# BQ34110.net
KiCad netlist of a schematic drawn in Altium Designer
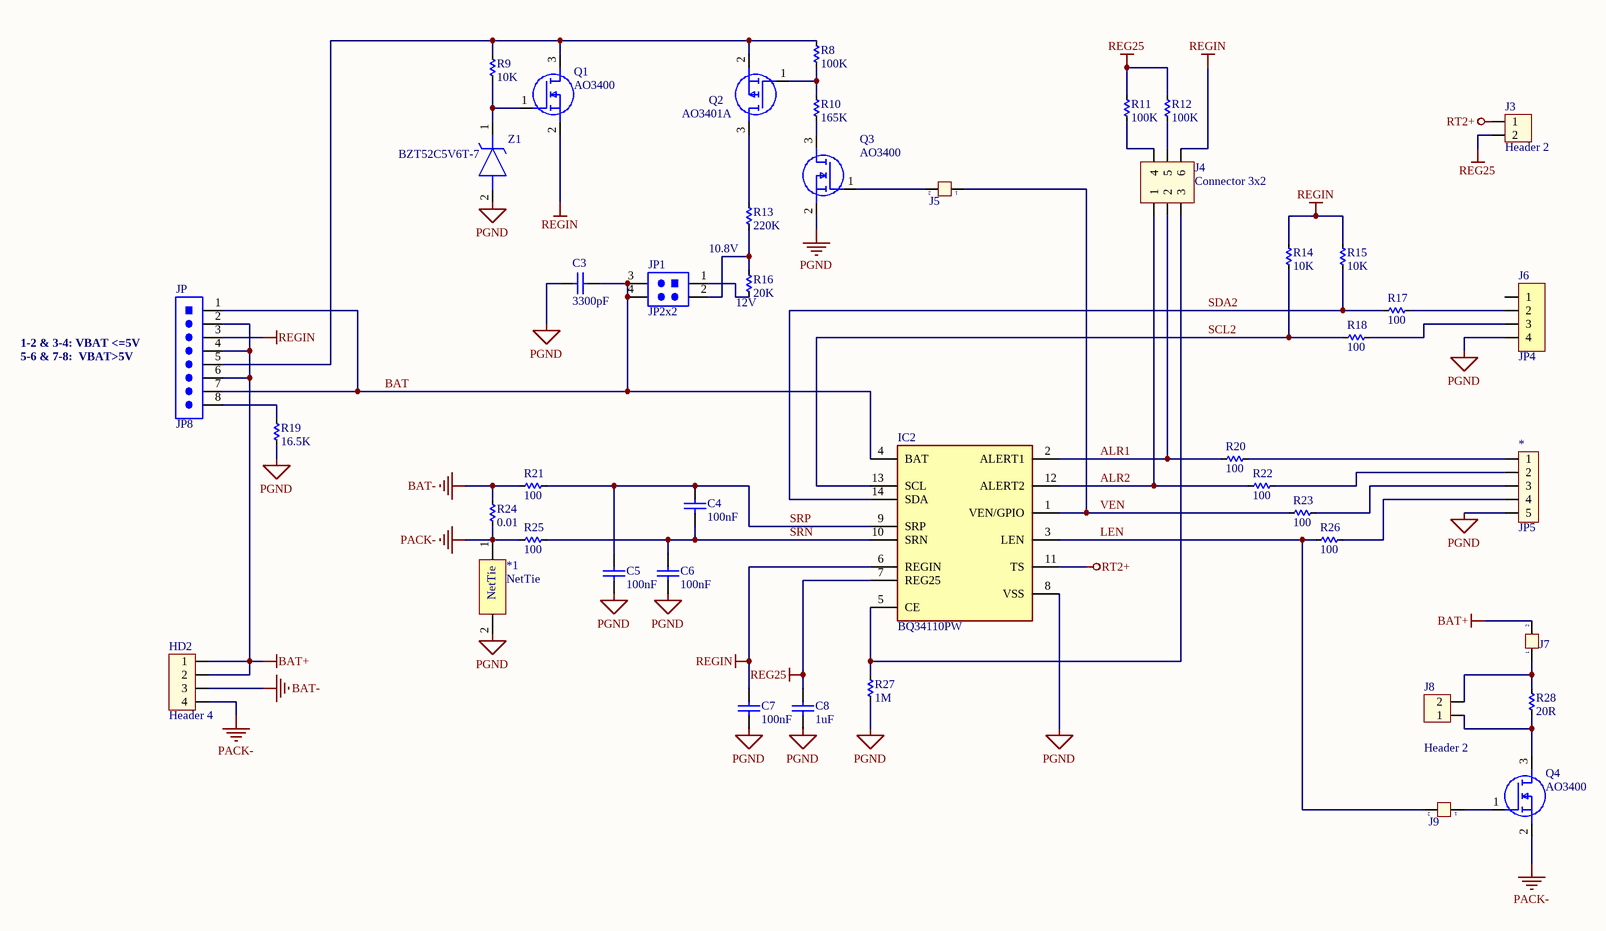
[diagram p0: BQ34110.SchDoc]

(export (version "E")
  (design (tool "Eeschema 10.0.6"))
  (components
    (comp (ref "*") (value "JP5") (footprint "JP5") (libsource (lib "syhaunguyen") (part "JP5")))
    (comp (ref "*1") (value "NetTie") (footprint "NetTie") (libsource (lib "PhanBach") (part "NetTie")))
    (comp (ref "C3")
      (value "3300pF")
      (footprint "0805 CAP")
      (fields (field (name "PUBLISHER") "Altium Limited"))
      (libsource (lib "ThinhNguyenLib") (part "CAP CERAMIC"))
    )
    (comp (ref "C4")
      (value "100nF")
      (footprint "0805 CAP")
      (fields (field (name "PUBLISHER") "Altium Limited"))
      (libsource (lib "ThinhNguyenLib") (part "CAP CERAMIC"))
    )
    (comp (ref "C5")
      (value "100nF")
      (footprint "0805 CAP")
      (fields (field (name "PUBLISHER") "Altium Limited"))
      (libsource (lib "ThinhNguyenLib") (part "CAP CERAMIC"))
    )
    (comp (ref "C6")
      (value "100nF")
      (footprint "0805 CAP")
      (fields (field (name "PUBLISHER") "Altium Limited"))
      (libsource (lib "ThinhNguyenLib") (part "CAP CERAMIC"))
    )
    (comp (ref "C7")
      (value "100nF")
      (footprint "0805 CAP")
      (fields (field (name "PUBLISHER") "Altium Limited"))
      (libsource (lib "ThinhNguyenLib") (part "CAP CERAMIC"))
    )
    (comp (ref "C8")
      (value "1uF")
      (footprint "0805 CAP")
      (fields (field (name "PUBLISHER") "Altium Limited"))
      (libsource (lib "ThinhNguyenLib") (part "CAP CERAMIC"))
    )
    (comp (ref "HD2")
      (value "Header 4")
      (footprint "HED4")
      (description "Header 4 (Green)")
      (libsource (lib "syhaunguyen") (part "Hed4"))
    )
    (comp (ref "IC2")
      (value "BQ34110PW")
      (footprint "SamacSys:SOP65P640X120-14N")
      (description "Integrated Circuit")
      (fields (field (name "MOUSER PART NUMBER") "595-BQ34110PW"))
      (libsource (lib "SamacSys") (part "BQ34110PW"))
    )
    (comp (ref "J3")
      (value "Header 2")
      (footprint "HED2B")
      (description "Header 2 (Green)")
      (libsource (lib "syhaunguyen") (part "Hed2"))
    )
    (comp (ref "J4")
      (value "Connector 3x2")
      (footprint "JP3x2")
      (libsource (lib "syhaunguyen") (part "JP3x2"))
    )
    (comp (ref "J5") (value "Jumper 2") (footprint "JP2") (libsource (lib "library") (part "JP 2")))
    (comp (ref "J6")
      (value "JP4")
      (footprint "JP4-C1T")
      (description "WR-PHD 2.54 mm Angled Socket Header")
      (fields
        (field (name "MANUFACTURER") "Würth Elektronik eiSos GmbH")
        (field (name "PARTNO") "613004143121")
        (field (name "CREATED BY") "Karrer Zheng")
      )
      (libsource (lib "LIBRARY1") (part "JP4"))
    )
    (comp (ref "J7") (value "Jumper 2") (footprint "JP2") (libsource (lib "") (part "JP 2_1")))
    (comp (ref "J8")
      (value "Header 2")
      (footprint "HED2B")
      (description "Header 2 (Green)")
      (libsource (lib "") (part "Hed2_1"))
    )
    (comp (ref "J9") (value "Jumper 2") (footprint "JP2") (libsource (lib "library") (part "JP 2")))
    (comp (ref "JP") (value "JP8") (footprint "JP8") (libsource (lib "PhanBach") (part "JP8")))
    (comp (ref "JP1") (value "JP2x2") (footprint "JP2X2") (libsource (lib "PhanBach") (part "JP2x2")))
    (comp (ref "Q1")
      (value "AO3400")
      (footprint "SamacSys:SOT95P280X125-3N")
      (description "MOSFET (N-Channel)")
      (libsource (lib "*") (part "AO3400"))
    )
    (comp (ref "Q2")
      (value "AO3401A")
      (footprint "SamacSys:SOT95P280X125-3N")
      (description "MOSFET (P-Channel)")
      (libsource (lib "*") (part "AO3401A"))
    )
    (comp (ref "Q3")
      (value "AO3400")
      (footprint "SamacSys:SOT95P280X125-3N")
      (description "MOSFET (N-Channel)")
      (libsource (lib "*") (part "AO3400"))
    )
    (comp (ref "Q4")
      (value "AO3400")
      (footprint "SamacSys:SOT95P280X125-3N")
      (description "MOSFET (N-Channel)")
      (libsource (lib "*") (part "AO3400"))
    )
    (comp (ref "R8")
      (value "100K")
      (footprint "RES-SMD-0805")
      (description "Resistor")
      (fields
        (field (name "MANUFACTURER") "Generic Components")
        (field (name "PUBLISHER") "Altium Hobart Technology Centre")
      )
      (libsource (lib "LIBRARY1") (part "Res-SMD"))
    )
    (comp (ref "R9")
      (value "10K")
      (footprint "RES-SMD-0805")
      (description "Resistor")
      (fields
        (field (name "MANUFACTURER") "Generic Components")
        (field (name "PUBLISHER") "Altium Hobart Technology Centre")
      )
      (libsource (lib "LIBRARY1") (part "Res-SMD"))
    )
    (comp (ref "R10")
      (value "165K")
      (footprint "RES-SMD-0805")
      (description "Resistor")
      (fields
        (field (name "MANUFACTURER") "Generic Components")
        (field (name "PUBLISHER") "Altium Hobart Technology Centre")
      )
      (libsource (lib "LIBRARY1") (part "Res-SMD"))
    )
    (comp (ref "R11")
      (value "100K")
      (footprint "RES-SMD-0805")
      (description "Resistor")
      (fields
        (field (name "MANUFACTURER") "Generic Components")
        (field (name "PUBLISHER") "Altium Hobart Technology Centre")
      )
      (libsource (lib "LIBRARY1") (part "Res-SMD"))
    )
    (comp (ref "R12")
      (value "100K")
      (footprint "RES-SMD-0805")
      (description "Resistor")
      (fields
        (field (name "MANUFACTURER") "Generic Components")
        (field (name "PUBLISHER") "Altium Hobart Technology Centre")
      )
      (libsource (lib "LIBRARY1") (part "Res-SMD"))
    )
    (comp (ref "R13")
      (value "220K")
      (footprint "RES-SMD-0805")
      (description "Resistor")
      (fields
        (field (name "MANUFACTURER") "Generic Components")
        (field (name "PUBLISHER") "Altium Hobart Technology Centre")
      )
      (libsource (lib "LIBRARY1") (part "Res-SMD"))
    )
    (comp (ref "R14")
      (value "10K")
      (footprint "RES-SMD-0805")
      (description "Resistor")
      (fields
        (field (name "MANUFACTURER") "Generic Components")
        (field (name "PUBLISHER") "Altium Hobart Technology Centre")
      )
      (libsource (lib "LIBRARY1") (part "Res-SMD"))
    )
    (comp (ref "R15")
      (value "10K")
      (footprint "RES-SMD-0805")
      (description "Resistor")
      (fields
        (field (name "MANUFACTURER") "Generic Components")
        (field (name "PUBLISHER") "Altium Hobart Technology Centre")
      )
      (libsource (lib "LIBRARY1") (part "Res-SMD"))
    )
    (comp (ref "R16")
      (value "20K")
      (footprint "RES-SMD-0805")
      (description "Resistor")
      (fields
        (field (name "MANUFACTURER") "Generic Components")
        (field (name "PUBLISHER") "Altium Hobart Technology Centre")
      )
      (libsource (lib "LIBRARY1") (part "Res-SMD"))
    )
    (comp (ref "R17")
      (value "100")
      (footprint "RES-SMD-0805")
      (description "Resistor")
      (fields
        (field (name "MANUFACTURER") "Generic Components")
        (field (name "PUBLISHER") "Altium Hobart Technology Centre")
      )
      (libsource (lib "LIBRARY1") (part "Res-SMD"))
    )
    (comp (ref "R18")
      (value "100")
      (footprint "RES-SMD-0805")
      (description "Resistor")
      (fields
        (field (name "MANUFACTURER") "Generic Components")
        (field (name "PUBLISHER") "Altium Hobart Technology Centre")
      )
      (libsource (lib "LIBRARY1") (part "Res-SMD"))
    )
    (comp (ref "R19")
      (value "16.5K")
      (footprint "RES-SMD-0805")
      (description "Resistor")
      (fields
        (field (name "MANUFACTURER") "Generic Components")
        (field (name "PUBLISHER") "Altium Hobart Technology Centre")
      )
      (libsource (lib "LIBRARY1") (part "Res-SMD"))
    )
    (comp (ref "R20")
      (value "100")
      (footprint "RES-SMD-0805")
      (description "Resistor")
      (fields
        (field (name "MANUFACTURER") "Generic Components")
        (field (name "PUBLISHER") "Altium Hobart Technology Centre")
      )
      (libsource (lib "LIBRARY1") (part "Res-SMD"))
    )
    (comp (ref "R21")
      (value "100")
      (footprint "RES-SMD-0805")
      (description "Resistor")
      (fields
        (field (name "MANUFACTURER") "Generic Components")
        (field (name "PUBLISHER") "Altium Hobart Technology Centre")
      )
      (libsource (lib "LIBRARY1") (part "Res-SMD"))
    )
    (comp (ref "R22")
      (value "100")
      (footprint "RES-SMD-0805")
      (description "Resistor")
      (fields
        (field (name "MANUFACTURER") "Generic Components")
        (field (name "PUBLISHER") "Altium Hobart Technology Centre")
      )
      (libsource (lib "LIBRARY1") (part "Res-SMD"))
    )
    (comp (ref "R23")
      (value "100")
      (footprint "RES-SMD-0805")
      (description "Resistor")
      (fields
        (field (name "MANUFACTURER") "Generic Components")
        (field (name "PUBLISHER") "Altium Hobart Technology Centre")
      )
      (libsource (lib "LIBRARY1") (part "Res-SMD"))
    )
    (comp (ref "R24")
      (value "0.01")
      (footprint "RES-SMD-0805")
      (description "Resistor")
      (fields
        (field (name "MANUFACTURER") "Generic Components")
        (field (name "PUBLISHER") "Altium Hobart Technology Centre")
      )
      (libsource (lib "LIBRARY1") (part "Res-SMD"))
    )
    (comp (ref "R25")
      (value "100")
      (footprint "RES-SMD-0805")
      (description "Resistor")
      (fields
        (field (name "MANUFACTURER") "Generic Components")
        (field (name "PUBLISHER") "Altium Hobart Technology Centre")
      )
      (libsource (lib "LIBRARY1") (part "Res-SMD"))
    )
    (comp (ref "R26")
      (value "100")
      (footprint "RES-SMD-0805")
      (description "Resistor")
      (fields
        (field (name "MANUFACTURER") "Generic Components")
        (field (name "PUBLISHER") "Altium Hobart Technology Centre")
      )
      (libsource (lib "LIBRARY1") (part "Res-SMD"))
    )
    (comp (ref "R27")
      (value "1M")
      (footprint "RES-SMD-0805")
      (description "Resistor")
      (fields
        (field (name "MANUFACTURER") "Generic Components")
        (field (name "PUBLISHER") "Altium Hobart Technology Centre")
      )
      (libsource (lib "LIBRARY1") (part "Res-SMD"))
    )
    (comp (ref "R28")
      (value "20R")
      (footprint "RES-SMD-2512")
      (description "Resistor")
      (fields
        (field (name "MANUFACTURER") "Generic Components")
        (field (name "PUBLISHER") "Altium Hobart Technology Centre")
      )
      (libsource (lib "LIBRARY1") (part "Res-SMD"))
    )
    (comp (ref "Z1")
      (value "BZT52C5V6T-7")
      (footprint "SamacSys:SODFL1608X65N")
      (description "Zener Diode")
      (fields (field (name "MOUSER PART NUMBER") "621-BZT52C5V6T-7"))
      (libsource (lib "*") (part "BZT52C5V6T-7"))
    )
  )
  (nets
    (net (code "1") (name "/ALR1") (class "Default")
      (node (ref "IC2") (pin "2") (pinfunction "ALERT1_2") (pintype "passive"))
      (node (ref "J4") (pin "5") (pinfunction "2_5") (pintype "passive"))
      (node (ref "R20") (pin "1") (pinfunction "1_1") (pintype "passive"))
    )
    (net (code "2") (name "/ALR2") (class "Default")
      (node (ref "IC2") (pin "12") (pinfunction "ALERT2_12") (pintype "passive"))
      (node (ref "J4") (pin "1") (pinfunction "1_1") (pintype "passive"))
      (node (ref "R22") (pin "1") (pinfunction "1_1") (pintype "passive"))
    )
    (net (code "3") (name "/BAT") (class "Default")
      (node (ref "C3") (pin "1") (pinfunction "1_1") (pintype "passive"))
      (node (ref "IC2") (pin "4") (pinfunction "BAT_4") (pintype "passive"))
      (node (ref "JP") (pin "1") (pinfunction "1_1") (pintype "passive"))
      (node (ref "JP") (pin "7") (pinfunction "7_7") (pintype "passive"))
      (node (ref "JP1") (pin "3") (pinfunction "3_3") (pintype "passive"))
      (node (ref "JP1") (pin "4") (pinfunction "4_4") (pintype "passive"))
    )
    (net (code "4") (name "/LEN") (class "Default")
      (node (ref "IC2") (pin "3") (pinfunction "LEN_3") (pintype "passive"))
      (node (ref "J9") (pin "2") (pinfunction "2_2") (pintype "passive"))
      (node (ref "R26") (pin "1") (pinfunction "1_1") (pintype "passive"))
    )
    (net (code "5") (name "/SCL2") (class "Default")
      (node (ref "IC2") (pin "13") (pinfunction "SCL_13") (pintype "passive"))
      (node (ref "R14") (pin "1") (pinfunction "1_1") (pintype "passive"))
      (node (ref "R18") (pin "1") (pinfunction "1_1") (pintype "passive"))
    )
    (net (code "6") (name "/SDA2") (class "Default")
      (node (ref "IC2") (pin "14") (pinfunction "SDA_14") (pintype "passive"))
      (node (ref "R15") (pin "1") (pinfunction "1_1") (pintype "passive"))
      (node (ref "R17") (pin "1") (pinfunction "1_1") (pintype "passive"))
    )
    (net (code "7") (name "/SRN") (class "Default")
      (node (ref "C4") (pin "2") (pinfunction "2_2") (pintype "passive"))
      (node (ref "C6") (pin "1") (pinfunction "1_1") (pintype "passive"))
      (node (ref "IC2") (pin "10") (pinfunction "SRN_10") (pintype "passive"))
      (node (ref "R25") (pin "2") (pinfunction "2_2") (pintype "passive"))
    )
    (net (code "8") (name "/SRP") (class "Default")
      (node (ref "C4") (pin "1") (pinfunction "1_1") (pintype "passive"))
      (node (ref "C5") (pin "1") (pinfunction "1_1") (pintype "passive"))
      (node (ref "IC2") (pin "9") (pinfunction "SRP_9") (pintype "passive"))
      (node (ref "R21") (pin "2") (pinfunction "2_2") (pintype "passive"))
    )
    (net (code "9") (name "/VEN") (class "Default")
      (node (ref "IC2") (pin "1") (pinfunction "VEN/GPIO_1") (pintype "passive"))
      (node (ref "J5") (pin "1") (pinfunction "1_1") (pintype "passive"))
      (node (ref "R23") (pin "1") (pinfunction "1_1") (pintype "passive"))
    )
    (net (code "10") (name "BAT+") (class "Default")
      (node (ref "HD2") (pin "1") (pinfunction "1_1") (pintype "passive"))
      (node (ref "HD2") (pin "2") (pinfunction "2_2") (pintype "passive"))
      (node (ref "J7") (pin "2") (pinfunction "2_2") (pintype "passive"))
      (node (ref "JP") (pin "2") (pinfunction "2_2") (pintype "passive"))
      (node (ref "JP") (pin "4") (pinfunction "4_4") (pintype "passive"))
      (node (ref "JP") (pin "6") (pinfunction "6_6") (pintype "passive"))
    )
    (net (code "11") (name "BAT-") (class "Default")
      (node (ref "HD2") (pin "3") (pinfunction "3_3") (pintype "passive"))
      (node (ref "R21") (pin "1") (pinfunction "1_1") (pintype "passive"))
      (node (ref "R24") (pin "1") (pinfunction "1_1") (pintype "passive"))
    )
    (net (code "12") (name "Net-(*-Pad1)") (class "Default")
      (node (ref "*") (pin "1") (pinfunction "1_1") (pintype "passive"))
      (node (ref "R20") (pin "2") (pinfunction "2_2") (pintype "passive"))
    )
    (net (code "13") (name "Net-(*-Pad2)") (class "Default")
      (node (ref "*") (pin "2") (pinfunction "2_2") (pintype "passive"))
      (node (ref "R22") (pin "2") (pinfunction "2_2") (pintype "passive"))
    )
    (net (code "14") (name "Net-(*-Pad3)") (class "Default")
      (node (ref "*") (pin "3") (pinfunction "3_3") (pintype "passive"))
      (node (ref "R23") (pin "2") (pinfunction "2_2") (pintype "passive"))
    )
    (net (code "15") (name "Net-(*-Pad4)") (class "Default")
      (node (ref "*") (pin "4") (pinfunction "4_4") (pintype "passive"))
      (node (ref "R26") (pin "2") (pinfunction "2_2") (pintype "passive"))
    )
    (net (code "16") (name "Net-(IC2-CE)") (class "Default")
      (node (ref "IC2") (pin "5") (pinfunction "CE_5") (pintype "passive"))
      (node (ref "J4") (pin "6") (pinfunction "3_6") (pintype "passive"))
      (node (ref "R27") (pin "1") (pinfunction "1_1") (pintype "passive"))
    )
    (net (code "17") (name "Net-(J4-5)") (class "Default")
      (node (ref "J4") (pin "2") (pinfunction "5_2") (pintype "passive"))
      (node (ref "R12") (pin "1") (pinfunction "1_1") (pintype "passive"))
    )
    (net (code "18") (name "Net-(J4-Pad4)") (class "Default")
      (node (ref "J4") (pin "4") (pinfunction "4_4") (pintype "passive"))
      (node (ref "R11") (pin "1") (pinfunction "1_1") (pintype "passive"))
    )
    (net (code "19") (name "Net-(J6-Pad2)") (class "Default")
      (node (ref "J6") (pin "2") (pinfunction "2_2") (pintype "passive"))
      (node (ref "R17") (pin "2") (pinfunction "2_2") (pintype "passive"))
    )
    (net (code "20") (name "Net-(J6-Pad3)") (class "Default")
      (node (ref "J6") (pin "3") (pinfunction "3_3") (pintype "passive"))
      (node (ref "R18") (pin "2") (pinfunction "2_2") (pintype "passive"))
    )
    (net (code "21") (name "Net-(J7-Pad1)") (class "Default")
      (node (ref "J7") (pin "1") (pinfunction "1_1") (pintype "passive"))
      (node (ref "J8") (pin "2") (pinfunction "2_2") (pintype "passive"))
      (node (ref "R28") (pin "2") (pinfunction "2_2") (pintype "passive"))
    )
    (net (code "22") (name "Net-(JP-Pad8)") (class "Default")
      (node (ref "JP") (pin "8") (pinfunction "8_8") (pintype "passive"))
      (node (ref "R19") (pin "2") (pinfunction "2_2") (pintype "passive"))
    )
    (net (code "23") (name "Net-(JP1-Pad1)") (class "Default")
      (node (ref "JP1") (pin "1") (pinfunction "1_1") (pintype "passive"))
      (node (ref "R16") (pin "1") (pinfunction "1_1") (pintype "passive"))
    )
    (net (code "24") (name "Net-(JP1-Pad2)") (class "Default")
      (node (ref "JP1") (pin "2") (pinfunction "2_2") (pintype "passive"))
      (node (ref "R13") (pin "1") (pinfunction "1_1") (pintype "passive"))
      (node (ref "R16") (pin "2") (pinfunction "2_2") (pintype "passive"))
    )
    (net (code "25") (name "Net-(Q1-D)") (class "Default")
      (node (ref "JP") (pin "5") (pinfunction "5_5") (pintype "passive"))
      (node (ref "Q1") (pin "3") (pinfunction "D_3") (pintype "passive"))
      (node (ref "Q2") (pin "2") (pinfunction "S_2") (pintype "passive"))
      (node (ref "R8") (pin "2") (pinfunction "2_2") (pintype "passive"))
      (node (ref "R9") (pin "2") (pinfunction "2_2") (pintype "passive"))
    )
    (net (code "26") (name "Net-(Q1-G)") (class "Default")
      (node (ref "Q1") (pin "1") (pinfunction "G_1") (pintype "passive"))
      (node (ref "R9") (pin "1") (pinfunction "1_1") (pintype "passive"))
      (node (ref "Z1") (pin "1") (pinfunction "K_1") (pintype "passive"))
    )
    (net (code "27") (name "Net-(Q2-D)") (class "Default")
      (node (ref "Q2") (pin "3") (pinfunction "D_3") (pintype "passive"))
      (node (ref "R13") (pin "2") (pinfunction "2_2") (pintype "passive"))
    )
    (net (code "28") (name "Net-(Q2-G)") (class "Default")
      (node (ref "Q2") (pin "1") (pinfunction "G_1") (pintype "passive"))
      (node (ref "R10") (pin "2") (pinfunction "2_2") (pintype "passive"))
      (node (ref "R8") (pin "1") (pinfunction "1_1") (pintype "passive"))
    )
    (net (code "29") (name "Net-(Q3-D)") (class "Default")
      (node (ref "Q3") (pin "3") (pinfunction "D_3") (pintype "passive"))
      (node (ref "R10") (pin "1") (pinfunction "1_1") (pintype "passive"))
    )
    (net (code "30") (name "Net-(Q3-G)") (class "Default")
      (node (ref "J5") (pin "2") (pinfunction "2_2") (pintype "passive"))
      (node (ref "Q3") (pin "1") (pinfunction "G_1") (pintype "passive"))
    )
    (net (code "31") (name "Net-(Q4-D)") (class "Default")
      (node (ref "J8") (pin "1") (pinfunction "1_1") (pintype "passive"))
      (node (ref "Q4") (pin "3") (pinfunction "D_3") (pintype "passive"))
      (node (ref "R28") (pin "1") (pinfunction "1_1") (pintype "passive"))
    )
    (net (code "32") (name "Net-(Q4-G)") (class "Default")
      (node (ref "J9") (pin "1") (pinfunction "1_1") (pintype "passive"))
      (node (ref "Q4") (pin "1") (pinfunction "G_1") (pintype "passive"))
    )
    (net (code "33") (name "PACK-") (class "Default")
      (node (ref "*1") (pin "1") (pinfunction "43_1") (pintype "passive"))
      (node (ref "HD2") (pin "4") (pinfunction "4_4") (pintype "passive"))
      (node (ref "Q4") (pin "2") (pinfunction "S_2") (pintype "passive"))
      (node (ref "R24") (pin "2") (pinfunction "2_2") (pintype "passive"))
      (node (ref "R25") (pin "1") (pinfunction "1_1") (pintype "passive"))
    )
    (net (code "34") (name "PGND") (class "Default")
      (node (ref "*") (pin "5") (pinfunction "5_5") (pintype "passive"))
      (node (ref "*1") (pin "2") (pinfunction "2_2") (pintype "passive"))
      (node (ref "C3") (pin "2") (pinfunction "2_2") (pintype "passive"))
      (node (ref "C5") (pin "2") (pinfunction "2_2") (pintype "passive"))
      (node (ref "C6") (pin "2") (pinfunction "2_2") (pintype "passive"))
      (node (ref "C7") (pin "2") (pinfunction "2_2") (pintype "passive"))
      (node (ref "C8") (pin "2") (pinfunction "2_2") (pintype "passive"))
      (node (ref "IC2") (pin "8") (pinfunction "VSS_8") (pintype "passive"))
      (node (ref "J6") (pin "4") (pinfunction "4_4") (pintype "passive"))
      (node (ref "Q3") (pin "2") (pinfunction "S_2") (pintype "passive"))
      (node (ref "R19") (pin "1") (pinfunction "1_1") (pintype "passive"))
      (node (ref "R27") (pin "2") (pinfunction "2_2") (pintype "passive"))
      (node (ref "Z1") (pin "2") (pinfunction "A_2") (pintype "passive"))
    )
    (net (code "35") (name "REG25") (class "Default")
      (node (ref "C8") (pin "1") (pinfunction "1_1") (pintype "passive"))
      (node (ref "IC2") (pin "7") (pinfunction "REG25_7") (pintype "passive"))
      (node (ref "J3") (pin "2") (pinfunction "2_2") (pintype "passive"))
      (node (ref "R11") (pin "2") (pinfunction "2_2") (pintype "passive"))
      (node (ref "R12") (pin "2") (pinfunction "2_2") (pintype "passive"))
    )
    (net (code "36") (name "REGIN") (class "Default")
      (node (ref "C7") (pin "1") (pinfunction "1_1") (pintype "passive"))
      (node (ref "IC2") (pin "6") (pinfunction "REGIN_6") (pintype "passive"))
      (node (ref "J4") (pin "3") (pinfunction "6_3") (pintype "passive"))
      (node (ref "JP") (pin "3") (pinfunction "3_3") (pintype "passive"))
      (node (ref "Q1") (pin "2") (pinfunction "S_2") (pintype "passive"))
      (node (ref "R14") (pin "2") (pinfunction "2_2") (pintype "passive"))
      (node (ref "R15") (pin "2") (pinfunction "2_2") (pintype "passive"))
    )
    (net (code "37") (name "RT2+") (class "Default")
      (node (ref "IC2") (pin "11") (pinfunction "TS_11") (pintype "passive"))
      (node (ref "J3") (pin "1") (pinfunction "1_1") (pintype "passive"))
    )
    (net (code "38") (name "unconnected-(J6-Pad1)") (class "Default")
      (node (ref "J6") (pin "1") (pinfunction "1_1") (pintype "passive"))
    )
  )
)
